# 5-3_3_Voltage_regulator.net
KiCad netlist of a schematic drawn in Altium Designer
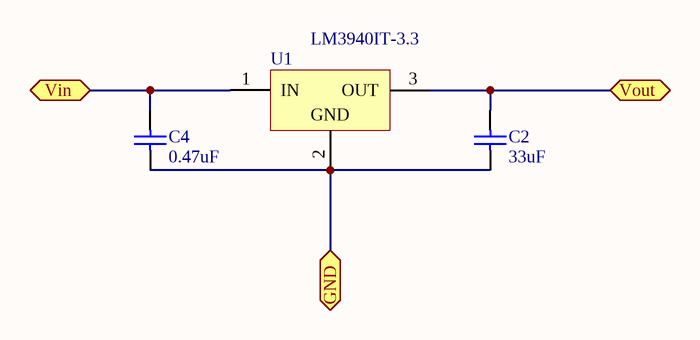
[diagram p0: 5-3.3 Voltage regulator.SchDoc]

(export (version "E")
  (design (tool "Eeschema 10.0.6"))
  (components
    (comp (ref "C2")
      (value "33uF")
      (footprint "RAD-0.3")
      (description "Capacitor")
      (fields (field (name "PUBLISHER") "Altium Limited"))
      (libsource (lib "Miscellaneous Devices") (part "Cap"))
    )
    (comp (ref "C4")
      (value "0.47uF")
      (footprint "RAD-0.3")
      (description "Capacitor")
      (fields (field (name "PUBLISHER") "Altium Limited"))
      (libsource (lib "Miscellaneous Devices") (part "Cap"))
    )
    (comp (ref "U1")
      (value "LM3940IT-3.3")
      (footprint "T03B")
      (description "1A Low Dropout Regulator for 5V to 3.3V Conversion, 3-pin TO-220")
      (fields (field (name "MANUFACTURER") "National Semiconductor"))
      (libsource (lib "National Semiconductor LDO") (part "LM3940IT-3.3"))
    )
  )
  (nets
    (net (code "1") (name "/GND") (class "Default")
      (node (ref "C2") (pin "1") (pinfunction "1_1") (pintype "passive"))
      (node (ref "C4") (pin "1") (pinfunction "1_1") (pintype "passive"))
      (node (ref "U1") (pin "2") (pinfunction "GND_2") (pintype "power_in"))
    )
    (net (code "2") (name "/Vin") (class "Default")
      (node (ref "C4") (pin "2") (pinfunction "2_2") (pintype "passive"))
      (node (ref "U1") (pin "1") (pinfunction "IN_1") (pintype "power_in"))
    )
    (net (code "3") (name "/Vout") (class "Default")
      (node (ref "C2") (pin "2") (pinfunction "2_2") (pintype "passive"))
      (node (ref "U1") (pin "3") (pinfunction "OUT_3") (pintype "power_in"))
    )
  )
)
